# jetson_agx_m_2.net
KiCad netlist of a schematic drawn in Altium Designer
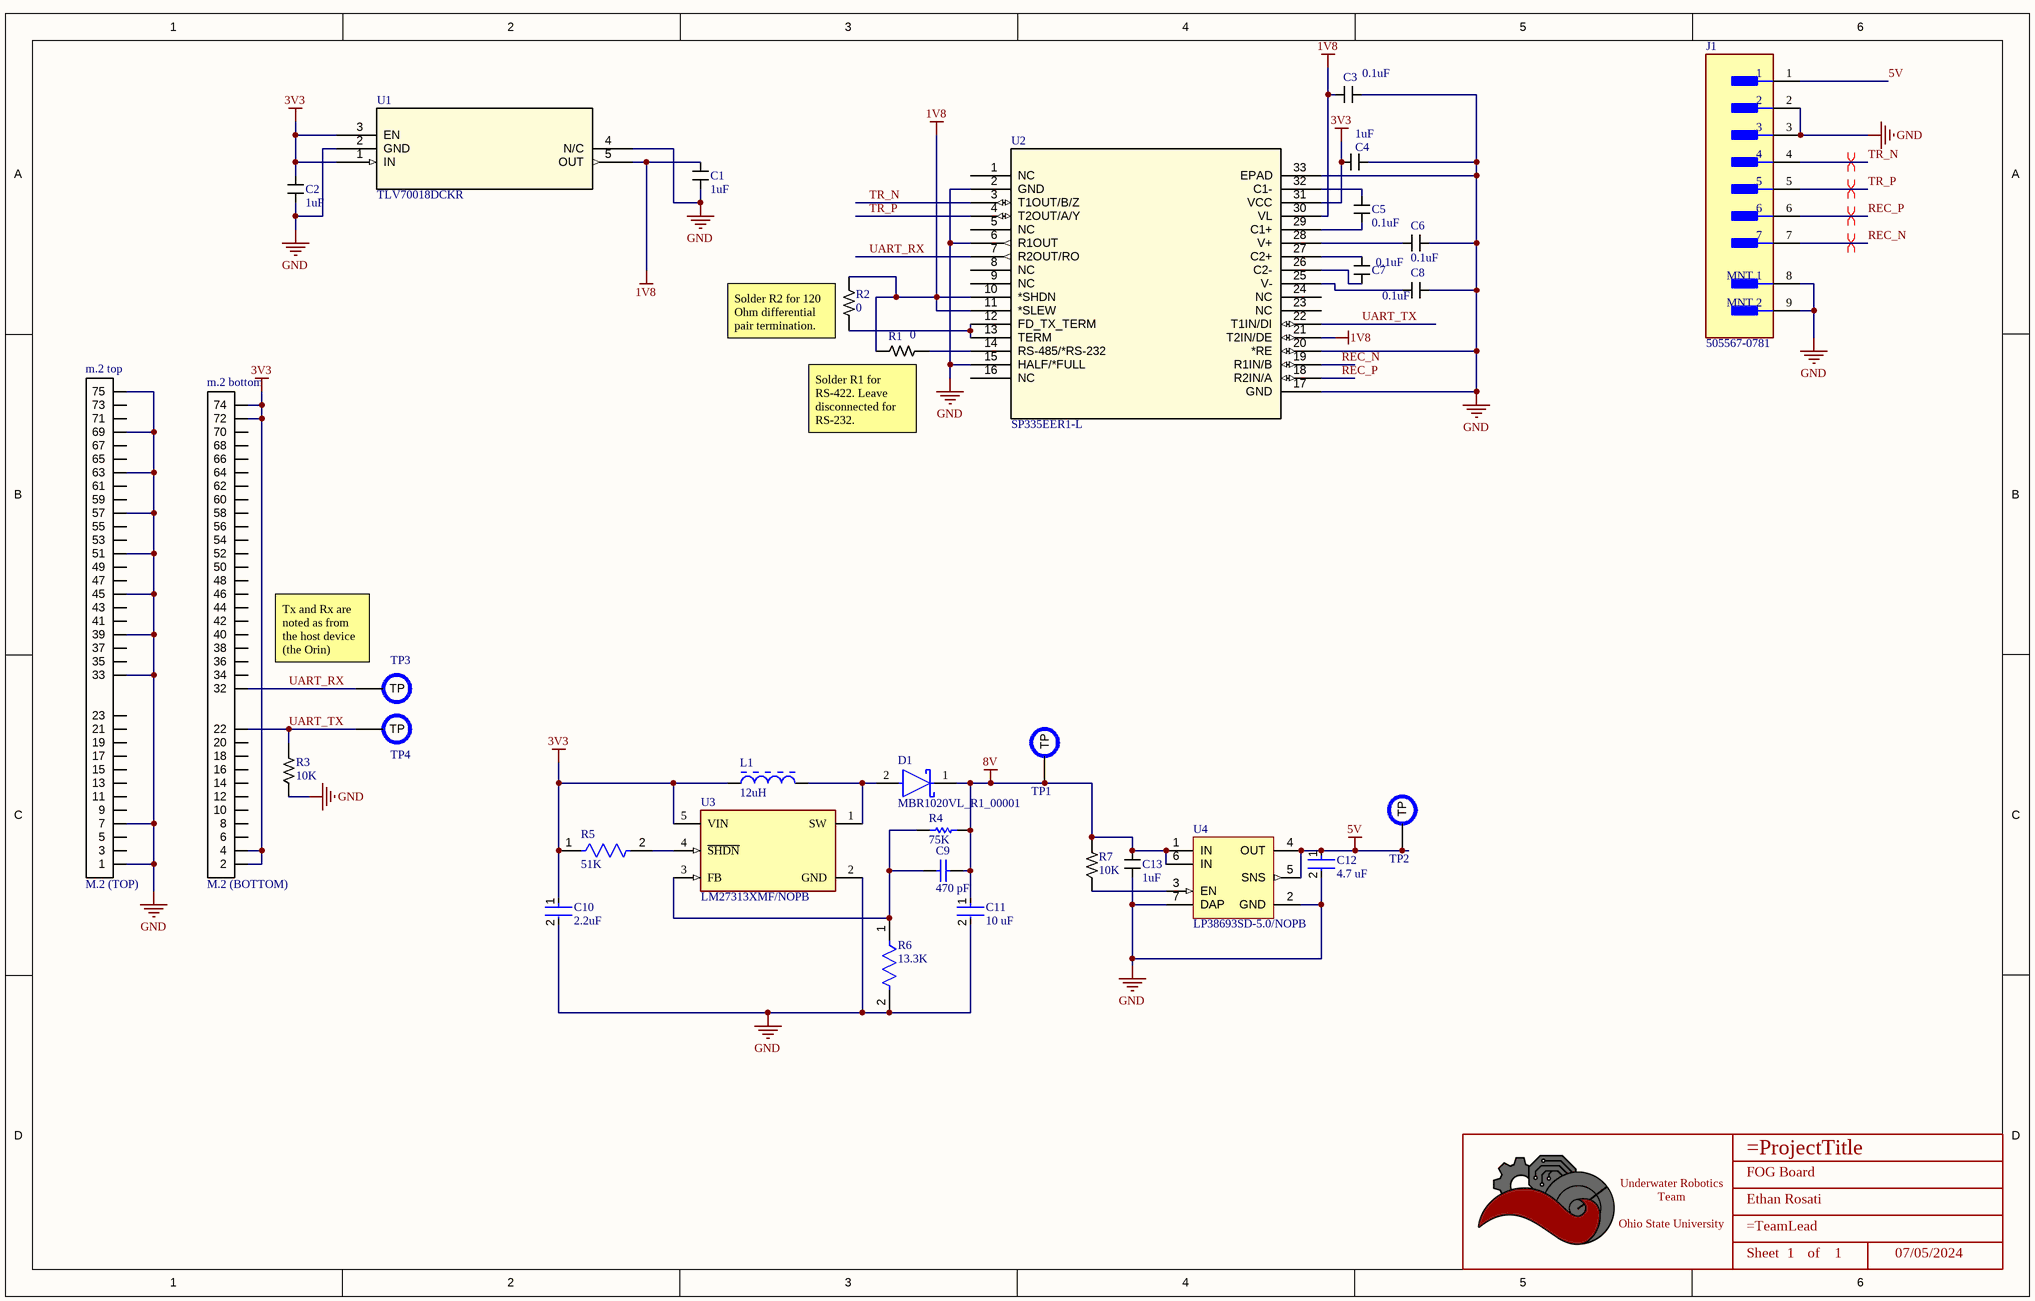
[diagram p0: jetson_agx_m.2.SchDoc]

(export (version "E")
  (design (tool "Eeschema 10.0.6"))
  (components
    (comp (ref "*")
      (value "Title_Block")
      (footprint "LOGO")
      (description "UWRT Schematic Title Block Template\r\n\r\nCreated June 2021, Dylan Trainor")
      (libsource (lib "UWRT") (part "Title_Block"))
    )
    (comp (ref "C1")
      (value "1uF")
      (footprint "CAPACITOR_0402")
      (description "Cap 1uF 16V +/-10%\r\nCeramic 0402")
      (fields
        (field (name "TOLERANCE") "+/- 10%")
        (field (name "VOLTAGE") "16V")
        (field (name "MADE BY") "Robert Pafford")
      )
      (libsource (lib "Capacitors") (part "CAPACITOR_1uF_0402"))
    )
    (comp (ref "C2")
      (value "1uF")
      (footprint "CAPACITOR_0402")
      (description "Cap 1uF 16V +/-10%\r\nCeramic 0402")
      (fields
        (field (name "TOLERANCE") "+/- 10%")
        (field (name "VOLTAGE") "16V")
        (field (name "MADE BY") "Robert Pafford")
      )
      (libsource (lib "Capacitors") (part "CAPACITOR_1uF_0402"))
    )
    (comp (ref "C3")
      (value "0.1uF")
      (footprint "CAPACITOR_0402")
      (description "Cap 100nF 25V +/-10%\r\nCeramic 0402")
      (fields
        (field (name "TOLERANCE") "+/- 10%")
        (field (name "VOLTAGE") "25V")
        (field (name "MADE BY") "Robert Pafford")
      )
      (libsource (lib "Capacitors") (part "CAPACITOR_0.1uF_0402"))
    )
    (comp (ref "C4")
      (value "1uF")
      (footprint "CAPACITOR_0402")
      (description "Cap 1uF 16V +/-10%\r\nCeramic 0402")
      (fields
        (field (name "TOLERANCE") "+/- 10%")
        (field (name "VOLTAGE") "16V")
        (field (name "MADE BY") "Robert Pafford")
      )
      (libsource (lib "Capacitors") (part "CAPACITOR_1uF_0402"))
    )
    (comp (ref "C5")
      (value "0.1uF")
      (footprint "CAPACITOR_0402")
      (description "Cap 100nF 25V +/-10%\r\nCeramic 0402")
      (fields
        (field (name "TOLERANCE") "+/- 10%")
        (field (name "VOLTAGE") "25V")
        (field (name "MADE BY") "Robert Pafford")
      )
      (libsource (lib "Capacitors") (part "CAPACITOR_0.1uF_0402"))
    )
    (comp (ref "C6")
      (value "0.1uF")
      (footprint "CAPACITOR_0402")
      (description "Cap 100nF 25V +/-10%\r\nCeramic 0402")
      (fields
        (field (name "TOLERANCE") "+/- 10%")
        (field (name "VOLTAGE") "25V")
        (field (name "MADE BY") "Robert Pafford")
      )
      (libsource (lib "Capacitors") (part "CAPACITOR_0.1uF_0402"))
    )
    (comp (ref "C7")
      (value "0.1uF")
      (footprint "CAPACITOR_0402")
      (description "Cap 100nF 25V +/-10%\r\nCeramic 0402")
      (fields
        (field (name "TOLERANCE") "+/- 10%")
        (field (name "VOLTAGE") "25V")
        (field (name "MADE BY") "Robert Pafford")
      )
      (libsource (lib "Capacitors") (part "CAPACITOR_0.1uF_0402"))
    )
    (comp (ref "C8")
      (value "0.1uF")
      (footprint "CAPACITOR_0402")
      (description "Cap 100nF 25V +/-10%\r\nCeramic 0402")
      (fields
        (field (name "TOLERANCE") "+/- 10%")
        (field (name "VOLTAGE") "25V")
        (field (name "MADE BY") "Robert Pafford")
      )
      (libsource (lib "Capacitors") (part "CAPACITOR_0.1uF_0402"))
    )
    (comp (ref "C9")
      (value "470 pF")
      (footprint "CAPC1005X55X25LL05T05")
      (fields (field (name "PART NUMBER") "VJ0402Y471KXQCW1BC") (field (name "MANUFACTURER") "Vitramon"))
      (libsource (lib "Altium Content Vault") (part "CAP"))
    )
    (comp (ref "C10")
      (value "2.2uF")
      (footprint "FP-GRT155-0_2-IPC_C")
      (description "Multi-Layer Ceramic Capacitor 2.2uF 10V X6S ±10% 0402 Paper T/R")
      (fields (field (name "TOLERANCE") "10%"))
      (libsource (lib "Altium Content Vault") (part "02cd4be3c70576c341d710602a673aa"))
    )
    (comp (ref "C11")
      (value "10 uF")
      (footprint "FP-CL07-IPC_C")
      (description "Cap Ceramic 10uF 10V X5R ±20% SMD 0402 +85°C Paper T/R")
      (fields (field (name "TOLERANCE") "20%"))
      (libsource (lib "Altium Content Vault") (part "b4654b650e69147ec39a6b967a45e02"))
    )
    (comp (ref "C12")
      (value "4.7 uF")
      (footprint "FP-CL282-IPC_C")
      (description "Cap Ceramic 4.7uF 10V X5R ±20% SMD 0402 +85°C Paper T/R")
      (fields (field (name "TOLERANCE") "20%"))
      (libsource (lib "Altium Content Vault") (part "b4654b650e69147ec39a6b967a45e02"))
    )
    (comp (ref "C13")
      (value "1uF")
      (footprint "CAPACITOR_0402")
      (description "Cap 1uF 16V +/-10%\r\nCeramic 0402")
      (fields
        (field (name "TOLERANCE") "+/- 10%")
        (field (name "VOLTAGE") "16V")
        (field (name "MADE BY") "Robert Pafford")
      )
      (libsource (lib "Capacitors") (part "CAPACITOR_1uF_0402"))
    )
    (comp (ref "D1")
      (value "MBR1020VL_R1_00001")
      (footprint "FP-MBR1020VL_R1_00001-MFG")
      (description "DIODE SCHOTTKY 20V 1A SOD123FL")
      (libsource (lib "Altium Content Vault") (part "c1678fac7984e62e0809fbf79c06691"))
    )
    (comp (ref "J1")
      (value "505567-0781")
      (footprint "FP-505567-0781-MFG")
      (libsource (lib "Altium Content Vault") (part "b0abd15a4b949e48c0a2e6945bb7dcd"))
    )
    (comp (ref "L1")
      (value "12uH")
      (footprint "BOUR-SDR0403-2_V")
      (fields (field (name "PARTNUMBER") "SDR0403-120ML") (field (name "MANUFACTURER") "Bourns"))
      (libsource (lib "Altium Content Vault") (part "BOUR-IND-2A"))
    )
    (comp (ref "m.2 bottom")
      (value "M.2 (BOTTOM)")
      (footprint "M.2 (bottom)")
      (fields (field (name "CREATED BY") "Ethan Rosati") (field (name "REVIEWED BY") "*"))
      (libsource (lib "Connectors") (part "M.2 (BOTTOM)"))
    )
    (comp (ref "m.2 top")
      (value "M.2 (TOP)")
      (footprint "M.2 (top)")
      (description "M.2 E-Key top fingers")
      (fields (field (name "CREATED BY") "Ethan Rosati") (field (name "REVIEWED BY") "*"))
      (libsource (lib "Connectors") (part "M.2 (TOP)"))
    )
    (comp (ref "R1")
      (value "0 Ohm 1% 1/16W")
      (footprint "RESISTOR_0402")
      (description "RES 0 OHM 1% 1/16W 0402")
      (fields
        (field (name "TOLERANCE") "+/- 1%")
        (field (name "VALUE  (OHMS)") "0")
        (field (name "MADE BY") "Robert Pafford")
      )
      (libsource (lib "Resistors") (part "RESISTOR_0_0402"))
    )
    (comp (ref "R2")
      (value "0 Ohm 1% 1/16W")
      (footprint "RESISTOR_0402")
      (description "RES 0 OHM 1% 1/16W 0402")
      (fields
        (field (name "TOLERANCE") "+/- 1%")
        (field (name "VALUE  (OHMS)") "0")
        (field (name "MADE BY") "Robert Pafford")
      )
      (libsource (lib "Resistors") (part "RESISTOR_0_0402"))
    )
    (comp (ref "R3")
      (value "10k Ohm 1% 1/16W")
      (footprint "RESISTOR_0402")
      (description "RES 10k OHM 1% 1/16W 0402")
      (fields
        (field (name "TOLERANCE") "+/- 1%")
        (field (name "VALUE  (OHMS)") "10K")
        (field (name "MADE BY") "Robert Pafford")
      )
      (libsource (lib "Resistors") (part "RESISTOR_10K_0402"))
    )
    (comp (ref "R4")
      (value "75K")
      (footprint "RESC1005X40X25NL10T10")
      (fields (field (name "PART NUMBER") "ERA-2AEB753X") (field (name "MANUFACTURER") "Panasonic"))
      (libsource (lib "Altium Content Vault") (part "RES"))
    )
    (comp (ref "R5")
      (value "51K")
      (footprint "FP-RMCF0402-MFG")
      (description "51kΩ ±5% 0.063W 0402 Thick Film Chip Resistor AEC-Q200 compliant")
      (fields (field (name "TOLERANCE") "5%"))
      (libsource (lib "Altium Content Vault") (part "1029c3af85768c4190bb7ad29bc67b5"))
    )
    (comp (ref "R6")
      (value "13.3K")
      (footprint "FP-CR0402-MFG")
      (description "Thick Film Chip Resistors 0402 13.3kΩ 0.0625W 1% 100ppm/°C")
      (fields (field (name "TOLERANCE") "1%"))
      (libsource (lib "Altium Content Vault") (part "1029c3af85768c4190bb7ad29bc67b5"))
    )
    (comp (ref "R7")
      (value "10k Ohm 1% 1/16W")
      (footprint "RESISTOR_0402")
      (description "RES 10k OHM 1% 1/16W 0402")
      (fields
        (field (name "TOLERANCE") "+/- 1%")
        (field (name "VALUE  (OHMS)") "10K")
        (field (name "MADE BY") "Robert Pafford")
      )
      (libsource (lib "Resistors") (part "RESISTOR_10K_0402"))
    )
    (comp (ref "TP1")
      (value "PCB Test Point")
      (footprint "TESTPOINT_1.2MM")
      (fields (field (name "MADE BY") "Robert Pafford"))
      (libsource (lib "Connectors") (part "TESTPOINT"))
    )
    (comp (ref "TP2")
      (value "PCB Test Point")
      (footprint "TESTPOINT_1.2MM")
      (fields (field (name "MADE BY") "Robert Pafford"))
      (libsource (lib "Connectors") (part "TESTPOINT"))
    )
    (comp (ref "TP3")
      (value "PCB Test Point")
      (footprint "TESTPOINT_1.2MM")
      (fields (field (name "MADE BY") "Robert Pafford"))
      (libsource (lib "Connectors") (part "TESTPOINT"))
    )
    (comp (ref "TP4")
      (value "PCB Test Point")
      (footprint "TESTPOINT_1.2MM")
      (fields (field (name "MADE BY") "Robert Pafford"))
      (libsource (lib "Connectors") (part "TESTPOINT"))
    )
    (comp (ref "U1")
      (value "TLV70018DCKR")
      (footprint "SOT-353")
      (description "Fixed Positive LDO Regulator, 1.8V, PMOS, PDSO5")
      (fields (field (name "MADE BY") "Ethan Rosati") (field (name "REVIEWED BY") "*"))
      (libsource (lib "Integrated Circuits") (part "TLV70018DCKR"))
    )
    (comp (ref "U2")
      (value "SP335EER1-L")
      (footprint "QFN-32")
      (description "1/1, 2/2 Transceiver Full RS232, RS422, RS485 32-QFN (5x5)")
      (fields (field (name "CREATED BY") "Ethan Rosati") (field (name "REVIEWED BY") "*"))
      (libsource (lib "Integrated Circuits") (part "SP335EER1-L"))
    )
    (comp (ref "U3")
      (value "LM27313XMF/NOPB")
      (footprint "FP-DBV0005A-IPC_A")
      (description "IC REG BOOST ADJ 800MA SOT23-5")
      (libsource (lib "Altium Content Vault") (part "169f9435efc31d3fe74d235977c1b19"))
    )
    (comp (ref "U4")
      (value "LP38693SD-5.0/NOPB")
      (footprint "NGG0006A_V")
      (fields (field (name "MANUFACTURER") "Texas Instruments"))
      (libsource (lib "Altium Content Vault") (part "PM-REG-LP38692-IL7"))
    )
  )
  (nets
    (net (code "1") (name "/REC_N") (class "Default")
      (node (ref "J1") (pin "7") (pinfunction "7_7") (pintype "passive"))
      (node (ref "U2") (pin "19") (pinfunction "R1IN/B_19") (pintype "bidirectional"))
    )
    (net (code "2") (name "/REC_P") (class "Default")
      (node (ref "J1") (pin "6") (pinfunction "6_6") (pintype "passive"))
      (node (ref "U2") (pin "18") (pinfunction "R2IN/A_18") (pintype "bidirectional"))
    )
    (net (code "3") (name "/TR_N") (class "Default")
      (node (ref "J1") (pin "4") (pinfunction "4_4") (pintype "passive"))
      (node (ref "U2") (pin "3") (pinfunction "T1OUT/B/Z_3") (pintype "bidirectional"))
    )
    (net (code "4") (name "/TR_P") (class "Default")
      (node (ref "J1") (pin "5") (pinfunction "5_5") (pintype "passive"))
      (node (ref "U2") (pin "4") (pinfunction "T2OUT/A/Y_4") (pintype "bidirectional"))
    )
    (net (code "5") (name "/UART_RX") (class "Default")
      (node (ref "TP3") (pin "TP") (pinfunction "TP_TP") (pintype "passive"))
      (node (ref "U2") (pin "7") (pinfunction "R2OUT/RO_7") (pintype "output"))
      (node (ref "m.2 bottom") (pin "32") (pinfunction "32_32") (pintype "passive"))
    )
    (net (code "6") (name "/UART_TX") (class "Default")
      (node (ref "R3") (pin "1") (pinfunction "1_1") (pintype "passive"))
      (node (ref "TP4") (pin "TP") (pinfunction "TP_TP") (pintype "passive"))
      (node (ref "U2") (pin "22") (pinfunction "T1IN/DI_22") (pintype "bidirectional"))
      (node (ref "m.2 bottom") (pin "22") (pinfunction "22_22") (pintype "passive"))
    )
    (net (code "7") (name "1V8") (class "Default")
      (node (ref "C1") (pin "1") (pinfunction "1_1") (pintype "passive"))
      (node (ref "C3") (pin "1") (pinfunction "1_1") (pintype "passive"))
      (node (ref "R1") (pin "2") (pinfunction "2_2") (pintype "passive"))
      (node (ref "R2") (pin "2") (pinfunction "2_2") (pintype "passive"))
      (node (ref "U1") (pin "5") (pinfunction "OUT_5") (pintype "output"))
      (node (ref "U2") (pin "10") (pinfunction "*SHDN_10") (pintype "passive"))
      (node (ref "U2") (pin "11") (pinfunction "*SLEW_11") (pintype "passive"))
      (node (ref "U2") (pin "21") (pinfunction "T2IN/DE_21") (pintype "bidirectional"))
      (node (ref "U2") (pin "30") (pinfunction "VL_30") (pintype "power_in"))
    )
    (net (code "8") (name "3V3") (class "Default")
      (node (ref "C10") (pin "1") (pinfunction "1_1") (pintype "passive"))
      (node (ref "C2") (pin "1") (pinfunction "1_1") (pintype "passive"))
      (node (ref "C4") (pin "1") (pinfunction "1_1") (pintype "passive"))
      (node (ref "L1") (pin "1") (pinfunction "1_1") (pintype "passive"))
      (node (ref "R5") (pin "1") (pinfunction "1_1") (pintype "passive"))
      (node (ref "U1") (pin "1") (pinfunction "IN_1") (pintype "input"))
      (node (ref "U1") (pin "3") (pinfunction "EN_3") (pintype "passive"))
      (node (ref "U2") (pin "31") (pinfunction "VCC_31") (pintype "power_in"))
      (node (ref "U3") (pin "5") (pinfunction "VIN_5") (pintype "power_in"))
      (node (ref "m.2 bottom") (pin "2") (pinfunction "2_2") (pintype "passive"))
      (node (ref "m.2 bottom") (pin "4") (pinfunction "4_4") (pintype "passive"))
      (node (ref "m.2 bottom") (pin "72") (pinfunction "72_72") (pintype "passive"))
      (node (ref "m.2 bottom") (pin "74") (pinfunction "74_74") (pintype "passive"))
    )
    (net (code "9") (name "5V") (class "Default")
      (node (ref "C12") (pin "1") (pinfunction "1_1") (pintype "passive"))
      (node (ref "J1") (pin "1") (pinfunction "1_1") (pintype "passive"))
      (node (ref "TP2") (pin "TP") (pinfunction "TP_TP") (pintype "passive"))
      (node (ref "U4") (pin "4") (pinfunction "OUT_4") (pintype "power_in"))
      (node (ref "U4") (pin "5") (pinfunction "SNS_5") (pintype "output"))
    )
    (net (code "10") (name "8V") (class "Default")
      (node (ref "C11") (pin "1") (pinfunction "1_1") (pintype "passive"))
      (node (ref "C13") (pin "1") (pinfunction "1_1") (pintype "passive"))
      (node (ref "C9") (pin "2") (pinfunction "2_2") (pintype "passive"))
      (node (ref "D1") (pin "1") (pinfunction "C_1") (pintype "passive"))
      (node (ref "R4") (pin "2") (pinfunction "2_2") (pintype "passive"))
      (node (ref "R7") (pin "1") (pinfunction "1_1") (pintype "passive"))
      (node (ref "TP1") (pin "TP") (pinfunction "TP_TP") (pintype "passive"))
      (node (ref "U4") (pin "1") (pinfunction "IN_1") (pintype "power_in"))
      (node (ref "U4") (pin "6") (pinfunction "IN_6") (pintype "power_in"))
    )
    (net (code "11") (name "GND") (class "Default")
      (node (ref "C1") (pin "2") (pinfunction "2_2") (pintype "passive"))
      (node (ref "C10") (pin "2") (pinfunction "2_2") (pintype "passive"))
      (node (ref "C11") (pin "2") (pinfunction "2_2") (pintype "passive"))
      (node (ref "C12") (pin "2") (pinfunction "2_2") (pintype "passive"))
      (node (ref "C13") (pin "2") (pinfunction "2_2") (pintype "passive"))
      (node (ref "C2") (pin "2") (pinfunction "2_2") (pintype "passive"))
      (node (ref "C3") (pin "2") (pinfunction "2_2") (pintype "passive"))
      (node (ref "C4") (pin "2") (pinfunction "2_2") (pintype "passive"))
      (node (ref "C6") (pin "2") (pinfunction "2_2") (pintype "passive"))
      (node (ref "C8") (pin "2") (pinfunction "2_2") (pintype "passive"))
      (node (ref "J1") (pin "2") (pinfunction "2_2") (pintype "passive"))
      (node (ref "J1") (pin "3") (pinfunction "3_3") (pintype "passive"))
      (node (ref "J1") (pin "8") (pinfunction "MNT_1_8") (pintype "passive"))
      (node (ref "J1") (pin "9") (pinfunction "MNT_2_9") (pintype "passive"))
      (node (ref "R3") (pin "2") (pinfunction "2_2") (pintype "passive"))
      (node (ref "R6") (pin "2") (pinfunction "2_2") (pintype "passive"))
      (node (ref "U1") (pin "2") (pinfunction "GND_2") (pintype "passive"))
      (node (ref "U1") (pin "4") (pinfunction "N/C_4") (pintype "power_in"))
      (node (ref "U2") (pin "15") (pinfunction "HALF/*FULL_15") (pintype "passive"))
      (node (ref "U2") (pin "17") (pinfunction "GND_17") (pintype "power_in"))
      (node (ref "U2") (pin "2") (pinfunction "GND_2") (pintype "power_in"))
      (node (ref "U2") (pin "20") (pinfunction "*RE_20") (pintype "bidirectional"))
      (node (ref "U2") (pin "33") (pinfunction "EPAD_33") (pintype "passive"))
      (node (ref "U2") (pin "6") (pinfunction "R1OUT_6") (pintype "output"))
      (node (ref "U3") (pin "2") (pinfunction "GND_2") (pintype "power_in"))
      (node (ref "U4") (pin "2") (pinfunction "GND_2") (pintype "power_in"))
      (node (ref "U4") (pin "7") (pinfunction "DAP_7") (pintype "power_in"))
      (node (ref "m.2 top") (pin "1") (pinfunction "1_1") (pintype "passive"))
      (node (ref "m.2 top") (pin "33") (pinfunction "33_33") (pintype "passive"))
      (node (ref "m.2 top") (pin "39") (pinfunction "39_39") (pintype "passive"))
      (node (ref "m.2 top") (pin "45") (pinfunction "45_45") (pintype "passive"))
      (node (ref "m.2 top") (pin "51") (pinfunction "51_51") (pintype "passive"))
      (node (ref "m.2 top") (pin "57") (pinfunction "57_57") (pintype "passive"))
      (node (ref "m.2 top") (pin "63") (pinfunction "63_63") (pintype "passive"))
      (node (ref "m.2 top") (pin "69") (pinfunction "69_69") (pintype "passive"))
      (node (ref "m.2 top") (pin "7") (pinfunction "7_7") (pintype "passive"))
      (node (ref "m.2 top") (pin "75") (pinfunction "75_75") (pintype "passive"))
    )
    (net (code "12") (name "Net-(D1-A)") (class "Default")
      (node (ref "D1") (pin "2") (pinfunction "A_2") (pintype "passive"))
      (node (ref "L1") (pin "2") (pinfunction "2_2") (pintype "passive"))
      (node (ref "U3") (pin "1") (pinfunction "SW_1") (pintype "power_in"))
    )
    (net (code "13") (name "Net-(U2-C1+)") (class "Default")
      (node (ref "C5") (pin "2") (pinfunction "2_2") (pintype "passive"))
      (node (ref "U2") (pin "29") (pinfunction "C1+_29") (pintype "passive"))
    )
    (net (code "14") (name "Net-(U2-C1-)") (class "Default")
      (node (ref "C5") (pin "1") (pinfunction "1_1") (pintype "passive"))
      (node (ref "U2") (pin "32") (pinfunction "C1-_32") (pintype "passive"))
    )
    (net (code "15") (name "Net-(U2-C2+)") (class "Default")
      (node (ref "C7") (pin "1") (pinfunction "1_1") (pintype "passive"))
      (node (ref "U2") (pin "27") (pinfunction "C2+_27") (pintype "passive"))
    )
    (net (code "16") (name "Net-(U2-C2-)") (class "Default")
      (node (ref "C7") (pin "2") (pinfunction "2_2") (pintype "passive"))
      (node (ref "U2") (pin "26") (pinfunction "C2-_26") (pintype "passive"))
    )
    (net (code "17") (name "Net-(U2-FD_TX_TERM)") (class "Default")
      (node (ref "R2") (pin "1") (pinfunction "1_1") (pintype "passive"))
      (node (ref "U2") (pin "12") (pinfunction "FD_TX_TERM_12") (pintype "passive"))
      (node (ref "U2") (pin "13") (pinfunction "TERM_13") (pintype "passive"))
    )
    (net (code "18") (name "Net-(U2-RS-485{slash}*RS-232)") (class "Default")
      (node (ref "R1") (pin "1") (pinfunction "1_1") (pintype "passive"))
      (node (ref "U2") (pin "14") (pinfunction "RS-485/*RS-232_14") (pintype "passive"))
    )
    (net (code "19") (name "Net-(U2-V+)") (class "Default")
      (node (ref "C6") (pin "1") (pinfunction "1_1") (pintype "passive"))
      (node (ref "U2") (pin "28") (pinfunction "V+_28") (pintype "power_in"))
    )
    (net (code "20") (name "Net-(U2-V-)") (class "Default")
      (node (ref "C8") (pin "1") (pinfunction "1_1") (pintype "passive"))
      (node (ref "U2") (pin "25") (pinfunction "V-_25") (pintype "power_in"))
    )
    (net (code "21") (name "Net-(U3-FB)") (class "Default")
      (node (ref "C9") (pin "1") (pinfunction "1_1") (pintype "passive"))
      (node (ref "R4") (pin "1") (pinfunction "1_1") (pintype "passive"))
      (node (ref "R6") (pin "1") (pinfunction "1_1") (pintype "passive"))
      (node (ref "U3") (pin "3") (pinfunction "FB_3") (pintype "input"))
    )
    (net (code "22") (name "Net-(U3-~{SHDN})") (class "Default")
      (node (ref "R5") (pin "2") (pinfunction "2_2") (pintype "passive"))
      (node (ref "U3") (pin "4") (pinfunction "~{SHDN}_4") (pintype "input"))
    )
    (net (code "23") (name "Net-(U4-EN)") (class "Default")
      (node (ref "R7") (pin "2") (pinfunction "2_2") (pintype "passive"))
      (node (ref "U4") (pin "3") (pinfunction "EN_3") (pintype "input"))
    )
    (net (code "24") (name "unconnected-(U2-NC-Pad1)") (class "Default")
      (node (ref "U2") (pin "1") (pinfunction "NC_1") (pintype "passive"))
    )
    (net (code "25") (name "unconnected-(U2-NC-Pad5)") (class "Default")
      (node (ref "U2") (pin "5") (pinfunction "NC_5") (pintype "passive"))
    )
    (net (code "26") (name "unconnected-(U2-NC-Pad8)") (class "Default")
      (node (ref "U2") (pin "8") (pinfunction "NC_8") (pintype "passive"))
    )
    (net (code "27") (name "unconnected-(U2-NC-Pad9)") (class "Default")
      (node (ref "U2") (pin "9") (pinfunction "NC_9") (pintype "passive"))
    )
    (net (code "28") (name "unconnected-(U2-NC-Pad16)") (class "Default")
      (node (ref "U2") (pin "16") (pinfunction "NC_16") (pintype "passive"))
    )
    (net (code "29") (name "unconnected-(U2-NC-Pad23)") (class "Default")
      (node (ref "U2") (pin "23") (pinfunction "NC_23") (pintype "passive"))
    )
    (net (code "30") (name "unconnected-(U2-NC-Pad24)") (class "Default")
      (node (ref "U2") (pin "24") (pinfunction "NC_24") (pintype "passive"))
    )
    (net (code "31") (name "unconnected-(m.2 bottom-Pad6)") (class "Default")
      (node (ref "m.2 bottom") (pin "6") (pinfunction "6_6") (pintype "passive"))
    )
    (net (code "32") (name "unconnected-(m.2 bottom-Pad8)") (class "Default")
      (node (ref "m.2 bottom") (pin "8") (pinfunction "8_8") (pintype "passive"))
    )
    (net (code "33") (name "unconnected-(m.2 bottom-Pad10)") (class "Default")
      (node (ref "m.2 bottom") (pin "10") (pinfunction "10_10") (pintype "passive"))
    )
    (net (code "34") (name "unconnected-(m.2 bottom-Pad12)") (class "Default")
      (node (ref "m.2 bottom") (pin "12") (pinfunction "12_12") (pintype "passive"))
    )
    (net (code "35") (name "unconnected-(m.2 bottom-Pad14)") (class "Default")
      (node (ref "m.2 bottom") (pin "14") (pinfunction "14_14") (pintype "passive"))
    )
    (net (code "36") (name "unconnected-(m.2 bottom-Pad16)") (class "Default")
      (node (ref "m.2 bottom") (pin "16") (pinfunction "16_16") (pintype "passive"))
    )
    (net (code "37") (name "unconnected-(m.2 bottom-Pad18)") (class "Default")
      (node (ref "m.2 bottom") (pin "18") (pinfunction "18_18") (pintype "passive"))
    )
    (net (code "38") (name "unconnected-(m.2 bottom-Pad20)") (class "Default")
      (node (ref "m.2 bottom") (pin "20") (pinfunction "20_20") (pintype "passive"))
    )
    (net (code "39") (name "unconnected-(m.2 bottom-Pad34)") (class "Default")
      (node (ref "m.2 bottom") (pin "34") (pinfunction "34_34") (pintype "passive"))
    )
    (net (code "40") (name "unconnected-(m.2 bottom-Pad36)") (class "Default")
      (node (ref "m.2 bottom") (pin "36") (pinfunction "36_36") (pintype "passive"))
    )
    (net (code "41") (name "unconnected-(m.2 bottom-Pad38)") (class "Default")
      (node (ref "m.2 bottom") (pin "38") (pinfunction "38_38") (pintype "passive"))
    )
    (net (code "42") (name "unconnected-(m.2 bottom-Pad40)") (class "Default")
      (node (ref "m.2 bottom") (pin "40") (pinfunction "40_40") (pintype "passive"))
    )
    (net (code "43") (name "unconnected-(m.2 bottom-Pad42)") (class "Default")
      (node (ref "m.2 bottom") (pin "42") (pinfunction "42_42") (pintype "passive"))
    )
    (net (code "44") (name "unconnected-(m.2 bottom-Pad44)") (class "Default")
      (node (ref "m.2 bottom") (pin "44") (pinfunction "44_44") (pintype "passive"))
    )
    (net (code "45") (name "unconnected-(m.2 bottom-Pad46)") (class "Default")
      (node (ref "m.2 bottom") (pin "46") (pinfunction "46_46") (pintype "passive"))
    )
    (net (code "46") (name "unconnected-(m.2 bottom-Pad48)") (class "Default")
      (node (ref "m.2 bottom") (pin "48") (pinfunction "48_48") (pintype "passive"))
    )
    (net (code "47") (name "unconnected-(m.2 bottom-Pad50)") (class "Default")
      (node (ref "m.2 bottom") (pin "50") (pinfunction "50_50") (pintype "passive"))
    )
    (net (code "48") (name "unconnected-(m.2 bottom-Pad52)") (class "Default")
      (node (ref "m.2 bottom") (pin "52") (pinfunction "52_52") (pintype "passive"))
    )
    (net (code "49") (name "unconnected-(m.2 bottom-Pad54)") (class "Default")
      (node (ref "m.2 bottom") (pin "54") (pinfunction "54_54") (pintype "passive"))
    )
    (net (code "50") (name "unconnected-(m.2 bottom-Pad56)") (class "Default")
      (node (ref "m.2 bottom") (pin "56") (pinfunction "56_56") (pintype "passive"))
    )
    (net (code "51") (name "unconnected-(m.2 bottom-Pad58)") (class "Default")
      (node (ref "m.2 bottom") (pin "58") (pinfunction "58_58") (pintype "passive"))
    )
    (net (code "52") (name "unconnected-(m.2 bottom-Pad60)") (class "Default")
      (node (ref "m.2 bottom") (pin "60") (pinfunction "60_60") (pintype "passive"))
    )
    (net (code "53") (name "unconnected-(m.2 bottom-Pad62)") (class "Default")
      (node (ref "m.2 bottom") (pin "62") (pinfunction "62_62") (pintype "passive"))
    )
    (net (code "54") (name "unconnected-(m.2 bottom-Pad64)") (class "Default")
      (node (ref "m.2 bottom") (pin "64") (pinfunction "64_64") (pintype "passive"))
    )
    (net (code "55") (name "unconnected-(m.2 bottom-Pad66)") (class "Default")
      (node (ref "m.2 bottom") (pin "66") (pinfunction "66_66") (pintype "passive"))
    )
    (net (code "56") (name "unconnected-(m.2 bottom-Pad68)") (class "Default")
      (node (ref "m.2 bottom") (pin "68") (pinfunction "68_68") (pintype "passive"))
    )
    (net (code "57") (name "unconnected-(m.2 bottom-Pad70)") (class "Default")
      (node (ref "m.2 bottom") (pin "70") (pinfunction "70_70") (pintype "passive"))
    )
    (net (code "58") (name "unconnected-(m.2 top-Pad3)") (class "Default")
      (node (ref "m.2 top") (pin "3") (pinfunction "3_3") (pintype "passive"))
    )
    (net (code "59") (name "unconnected-(m.2 top-Pad5)") (class "Default")
      (node (ref "m.2 top") (pin "5") (pinfunction "5_5") (pintype "passive"))
    )
    (net (code "60") (name "unconnected-(m.2 top-Pad9)") (class "Default")
      (node (ref "m.2 top") (pin "9") (pinfunction "9_9") (pintype "passive"))
    )
    (net (code "61") (name "unconnected-(m.2 top-Pad11)") (class "Default")
      (node (ref "m.2 top") (pin "11") (pinfunction "11_11") (pintype "passive"))
    )
    (net (code "62") (name "unconnected-(m.2 top-Pad13)") (class "Default")
      (node (ref "m.2 top") (pin "13") (pinfunction "13_13") (pintype "passive"))
    )
    (net (code "63") (name "unconnected-(m.2 top-Pad15)") (class "Default")
      (node (ref "m.2 top") (pin "15") (pinfunction "15_15") (pintype "passive"))
    )
    (net (code "64") (name "unconnected-(m.2 top-Pad17)") (class "Default")
      (node (ref "m.2 top") (pin "17") (pinfunction "17_17") (pintype "passive"))
    )
    (net (code "65") (name "unconnected-(m.2 top-Pad19)") (class "Default")
      (node (ref "m.2 top") (pin "19") (pinfunction "19_19") (pintype "passive"))
    )
    (net (code "66") (name "unconnected-(m.2 top-Pad21)") (class "Default")
      (node (ref "m.2 top") (pin "21") (pinfunction "21_21") (pintype "passive"))
    )
    (net (code "67") (name "unconnected-(m.2 top-Pad23)") (class "Default")
      (node (ref "m.2 top") (pin "23") (pinfunction "23_23") (pintype "passive"))
    )
    (net (code "68") (name "unconnected-(m.2 top-Pad35)") (class "Default")
      (node (ref "m.2 top") (pin "35") (pinfunction "35_35") (pintype "passive"))
    )
    (net (code "69") (name "unconnected-(m.2 top-Pad37)") (class "Default")
      (node (ref "m.2 top") (pin "37") (pinfunction "37_37") (pintype "passive"))
    )
    (net (code "70") (name "unconnected-(m.2 top-Pad41)") (class "Default")
      (node (ref "m.2 top") (pin "41") (pinfunction "41_41") (pintype "passive"))
    )
    (net (code "71") (name "unconnected-(m.2 top-Pad43)") (class "Default")
      (node (ref "m.2 top") (pin "43") (pinfunction "43_43") (pintype "passive"))
    )
    (net (code "72") (name "unconnected-(m.2 top-Pad47)") (class "Default")
      (node (ref "m.2 top") (pin "47") (pinfunction "47_47") (pintype "passive"))
    )
    (net (code "73") (name "unconnected-(m.2 top-Pad49)") (class "Default")
      (node (ref "m.2 top") (pin "49") (pinfunction "49_49") (pintype "passive"))
    )
    (net (code "74") (name "unconnected-(m.2 top-Pad53)") (class "Default")
      (node (ref "m.2 top") (pin "53") (pinfunction "53_53") (pintype "passive"))
    )
    (net (code "75") (name "unconnected-(m.2 top-Pad55)") (class "Default")
      (node (ref "m.2 top") (pin "55") (pinfunction "55_55") (pintype "passive"))
    )
    (net (code "76") (name "unconnected-(m.2 top-Pad59)") (class "Default")
      (node (ref "m.2 top") (pin "59") (pinfunction "59_59") (pintype "passive"))
    )
    (net (code "77") (name "unconnected-(m.2 top-Pad61)") (class "Default")
      (node (ref "m.2 top") (pin "61") (pinfunction "61_61") (pintype "passive"))
    )
    (net (code "78") (name "unconnected-(m.2 top-Pad65)") (class "Default")
      (node (ref "m.2 top") (pin "65") (pinfunction "65_65") (pintype "passive"))
    )
    (net (code "79") (name "unconnected-(m.2 top-Pad67)") (class "Default")
      (node (ref "m.2 top") (pin "67") (pinfunction "67_67") (pintype "passive"))
    )
    (net (code "80") (name "unconnected-(m.2 top-Pad71)") (class "Default")
      (node (ref "m.2 top") (pin "71") (pinfunction "71_71") (pintype "passive"))
    )
    (net (code "81") (name "unconnected-(m.2 top-Pad73)") (class "Default")
      (node (ref "m.2 top") (pin "73") (pinfunction "73_73") (pintype "passive"))
    )
  )
)
